# v8_8_controler.net
KiCad netlist of a schematic drawn in EAGLE
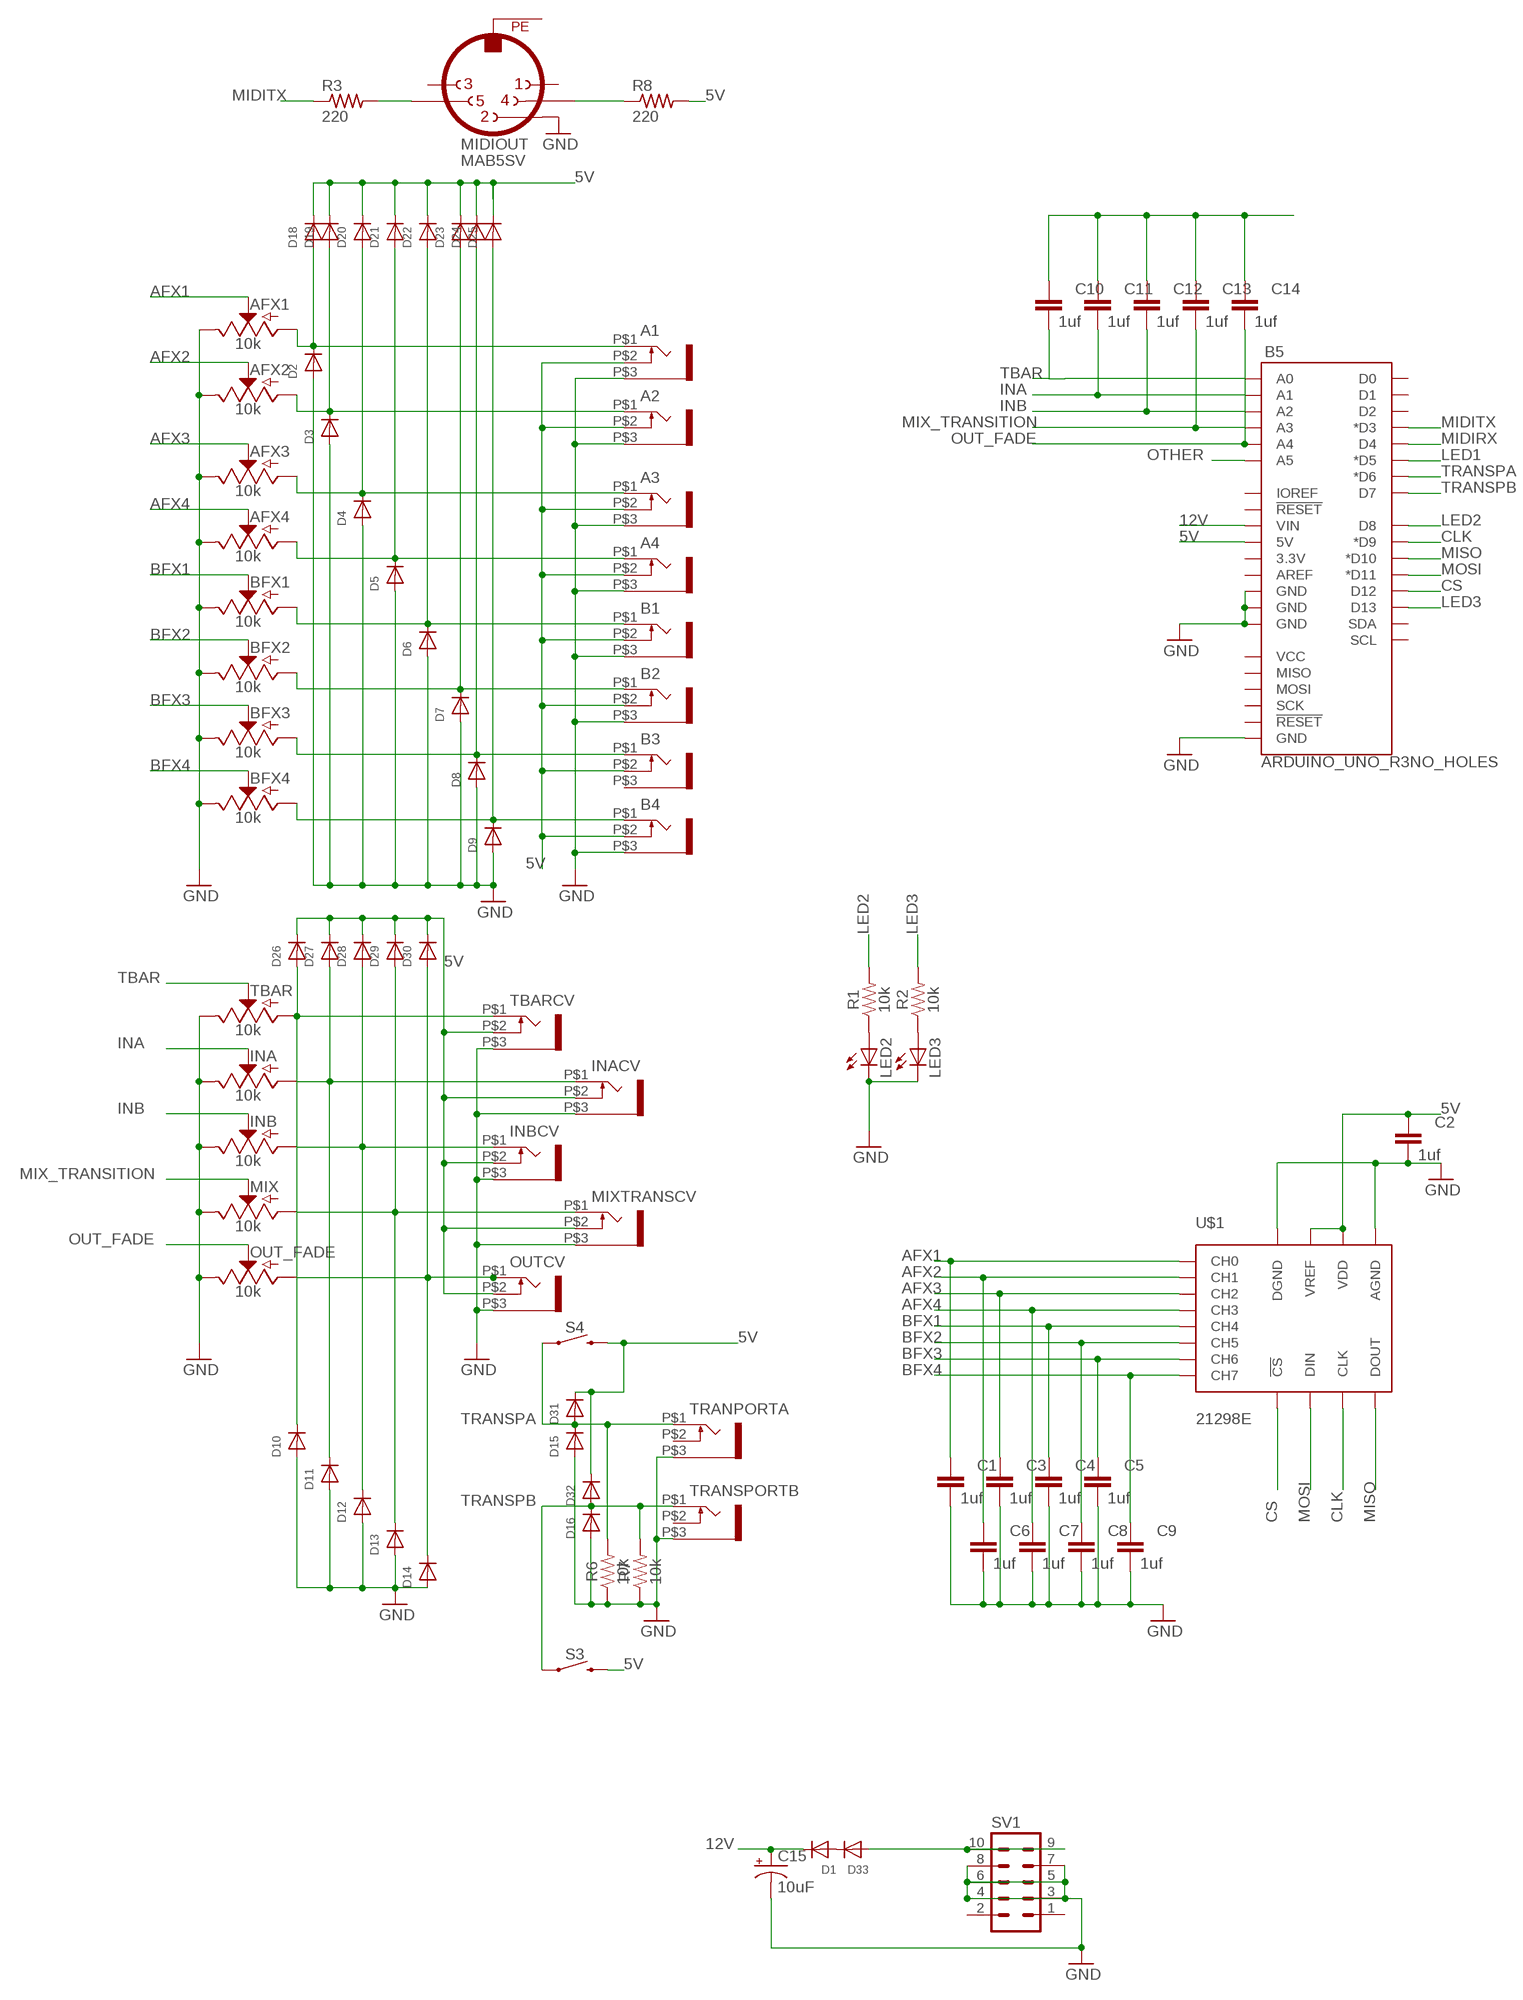
[diagram p0: schematic, sheet 1]

(export (version "E")
  (design (tool "Eeschema 10.0.6"))
  (components
    (comp (ref "A1")
      (value "WQP-PJ301M-12_JACK")
      (footprint "eagle-import:WQP-PJ301M-12_JACK")
      (fields (field (name "SPICEPREFIX") "U"))
      (libsource (lib "eagle-import") (part "WQP-PJ301M-12_JACK"))
    )
    (comp (ref "A2")
      (value "WQP-PJ301M-12_JACK")
      (footprint "eagle-import:WQP-PJ301M-12_JACK")
      (fields (field (name "SPICEPREFIX") "U"))
      (libsource (lib "eagle-import") (part "WQP-PJ301M-12_JACK"))
    )
    (comp (ref "A3")
      (value "WQP-PJ301M-12_JACK")
      (footprint "eagle-import:WQP-PJ301M-12_JACK")
      (fields (field (name "SPICEPREFIX") "U"))
      (libsource (lib "eagle-import") (part "WQP-PJ301M-12_JACK"))
    )
    (comp (ref "A4")
      (value "WQP-PJ301M-12_JACK")
      (footprint "eagle-import:WQP-PJ301M-12_JACK")
      (fields (field (name "SPICEPREFIX") "U"))
      (libsource (lib "eagle-import") (part "WQP-PJ301M-12_JACK"))
    )
    (comp (ref "AFX1")
      (value "10k")
      (footprint "eagle-import:POT-PTH-ALPS")
      (libsource (lib "eagle-import") (part "POTENTIOMETER-PTH-9MM-1/20W-20%"))
    )
    (comp (ref "AFX2")
      (value "10k")
      (footprint "eagle-import:POT-PTH-ALPS")
      (libsource (lib "eagle-import") (part "POTENTIOMETER-PTH-9MM-1/20W-20%"))
    )
    (comp (ref "AFX3")
      (value "10k")
      (footprint "eagle-import:POT-PTH-ALPS")
      (libsource (lib "eagle-import") (part "POTENTIOMETER-PTH-9MM-1/20W-20%"))
    )
    (comp (ref "AFX4")
      (value "10k")
      (footprint "eagle-import:POT-PTH-ALPS")
      (libsource (lib "eagle-import") (part "POTENTIOMETER-PTH-9MM-1/20W-20%"))
    )
    (comp (ref "B1")
      (value "WQP-PJ301M-12_JACK")
      (footprint "eagle-import:WQP-PJ301M-12_JACK")
      (fields (field (name "SPICEPREFIX") "U"))
      (libsource (lib "eagle-import") (part "WQP-PJ301M-12_JACK"))
    )
    (comp (ref "B2")
      (value "WQP-PJ301M-12_JACK")
      (footprint "eagle-import:WQP-PJ301M-12_JACK")
      (fields (field (name "SPICEPREFIX") "U"))
      (libsource (lib "eagle-import") (part "WQP-PJ301M-12_JACK"))
    )
    (comp (ref "B3")
      (value "WQP-PJ301M-12_JACK")
      (footprint "eagle-import:WQP-PJ301M-12_JACK")
      (fields (field (name "SPICEPREFIX") "U"))
      (libsource (lib "eagle-import") (part "WQP-PJ301M-12_JACK"))
    )
    (comp (ref "B4")
      (value "WQP-PJ301M-12_JACK")
      (footprint "eagle-import:WQP-PJ301M-12_JACK")
      (fields (field (name "SPICEPREFIX") "U"))
      (libsource (lib "eagle-import") (part "WQP-PJ301M-12_JACK"))
    )
    (comp (ref "B5")
      (value "ARDUINO_UNO_R3NO_HOLES")
      (footprint "eagle-import:ARDUINO_R3_NO_HOLES")
      (libsource (lib "eagle-import") (part "ARDUINO_UNO_R3NO_HOLES"))
    )
    (comp (ref "BFX1")
      (value "10k")
      (footprint "eagle-import:POT-PTH-ALPS")
      (libsource (lib "eagle-import") (part "POTENTIOMETER-PTH-9MM-1/20W-20%"))
    )
    (comp (ref "BFX2")
      (value "10k")
      (footprint "eagle-import:POT-PTH-ALPS")
      (libsource (lib "eagle-import") (part "POTENTIOMETER-PTH-9MM-1/20W-20%"))
    )
    (comp (ref "BFX3")
      (value "10k")
      (footprint "eagle-import:POT-PTH-ALPS")
      (libsource (lib "eagle-import") (part "POTENTIOMETER-PTH-9MM-1/20W-20%"))
    )
    (comp (ref "BFX4")
      (value "10k")
      (footprint "eagle-import:POT-PTH-ALPS")
      (libsource (lib "eagle-import") (part "POTENTIOMETER-PTH-9MM-1/20W-20%"))
    )
    (comp (ref "C1")
      (value "1uf")
      (footprint "eagle-import:0805")
      (libsource (lib "eagle-import") (part "0.33UF/330NF-0805-50V-10%"))
    )
    (comp (ref "C2")
      (value "1uf")
      (footprint "eagle-import:0805")
      (libsource (lib "eagle-import") (part "0.33UF/330NF-0805-50V-10%"))
    )
    (comp (ref "C3")
      (value "1uf")
      (footprint "eagle-import:0805")
      (libsource (lib "eagle-import") (part "0.33UF/330NF-0805-50V-10%"))
    )
    (comp (ref "C4")
      (value "1uf")
      (footprint "eagle-import:0805")
      (libsource (lib "eagle-import") (part "0.33UF/330NF-0805-50V-10%"))
    )
    (comp (ref "C5")
      (value "1uf")
      (footprint "eagle-import:0805")
      (libsource (lib "eagle-import") (part "0.33UF/330NF-0805-50V-10%"))
    )
    (comp (ref "C6")
      (value "1uf")
      (footprint "eagle-import:0805")
      (libsource (lib "eagle-import") (part "0.33UF/330NF-0805-50V-10%"))
    )
    (comp (ref "C7")
      (value "1uf")
      (footprint "eagle-import:0805")
      (libsource (lib "eagle-import") (part "0.33UF/330NF-0805-50V-10%"))
    )
    (comp (ref "C8")
      (value "1uf")
      (footprint "eagle-import:0805")
      (libsource (lib "eagle-import") (part "0.33UF/330NF-0805-50V-10%"))
    )
    (comp (ref "C9")
      (value "1uf")
      (footprint "eagle-import:0805")
      (libsource (lib "eagle-import") (part "0.33UF/330NF-0805-50V-10%"))
    )
    (comp (ref "C10")
      (value "1uf")
      (footprint "eagle-import:0805")
      (libsource (lib "eagle-import") (part "0.33UF/330NF-0805-50V-10%"))
    )
    (comp (ref "C11")
      (value "1uf")
      (footprint "eagle-import:0805")
      (libsource (lib "eagle-import") (part "0.33UF/330NF-0805-50V-10%"))
    )
    (comp (ref "C12")
      (value "1uf")
      (footprint "eagle-import:0805")
      (libsource (lib "eagle-import") (part "0.33UF/330NF-0805-50V-10%"))
    )
    (comp (ref "C13")
      (value "1uf")
      (footprint "eagle-import:0805")
      (libsource (lib "eagle-import") (part "0.33UF/330NF-0805-50V-10%"))
    )
    (comp (ref "C14")
      (value "1uf")
      (footprint "eagle-import:0805")
      (libsource (lib "eagle-import") (part "0.33UF/330NF-0805-50V-10%"))
    )
    (comp (ref "C15")
      (value "10uF")
      (footprint "eagle-import:EIA3528")
      (libsource (lib "eagle-import") (part "10UF-POLAR-EIA3528-20V-10%(TANT)"))
    )
    (comp (ref "D1")
      (value "DIODE_SOD-123FL")
      (footprint "eagle-import:SOD-123FL")
      (libsource (lib "eagle-import") (part "DIODE_SOD-123FL"))
    )
    (comp (ref "D2")
      (value "DIODE_SOD-123FL")
      (footprint "eagle-import:SOD-123FL")
      (libsource (lib "eagle-import") (part "DIODE_SOD-123FL"))
    )
    (comp (ref "D3")
      (value "DIODE_SOD-123FL")
      (footprint "eagle-import:SOD-123FL")
      (libsource (lib "eagle-import") (part "DIODE_SOD-123FL"))
    )
    (comp (ref "D4")
      (value "DIODE_SOD-123FL")
      (footprint "eagle-import:SOD-123FL")
      (libsource (lib "eagle-import") (part "DIODE_SOD-123FL"))
    )
    (comp (ref "D5")
      (value "DIODE_SOD-123FL")
      (footprint "eagle-import:SOD-123FL")
      (libsource (lib "eagle-import") (part "DIODE_SOD-123FL"))
    )
    (comp (ref "D6")
      (value "DIODE_SOD-123FL")
      (footprint "eagle-import:SOD-123FL")
      (libsource (lib "eagle-import") (part "DIODE_SOD-123FL"))
    )
    (comp (ref "D7")
      (value "DIODE_SOD-123FL")
      (footprint "eagle-import:SOD-123FL")
      (libsource (lib "eagle-import") (part "DIODE_SOD-123FL"))
    )
    (comp (ref "D8")
      (value "DIODE_SOD-123FL")
      (footprint "eagle-import:SOD-123FL")
      (libsource (lib "eagle-import") (part "DIODE_SOD-123FL"))
    )
    (comp (ref "D9")
      (value "DIODE_SOD-123FL")
      (footprint "eagle-import:SOD-123FL")
      (libsource (lib "eagle-import") (part "DIODE_SOD-123FL"))
    )
    (comp (ref "D10")
      (value "DIODE_SOD-123FL")
      (footprint "eagle-import:SOD-123FL")
      (libsource (lib "eagle-import") (part "DIODE_SOD-123FL"))
    )
    (comp (ref "D11")
      (value "DIODE_SOD-123FL")
      (footprint "eagle-import:SOD-123FL")
      (libsource (lib "eagle-import") (part "DIODE_SOD-123FL"))
    )
    (comp (ref "D12")
      (value "DIODE_SOD-123FL")
      (footprint "eagle-import:SOD-123FL")
      (libsource (lib "eagle-import") (part "DIODE_SOD-123FL"))
    )
    (comp (ref "D13")
      (value "DIODE_SOD-123FL")
      (footprint "eagle-import:SOD-123FL")
      (libsource (lib "eagle-import") (part "DIODE_SOD-123FL"))
    )
    (comp (ref "D14")
      (value "DIODE_SOD-123FL")
      (footprint "eagle-import:SOD-123FL")
      (libsource (lib "eagle-import") (part "DIODE_SOD-123FL"))
    )
    (comp (ref "D15")
      (value "DIODE_SOD-123FL")
      (footprint "eagle-import:SOD-123FL")
      (libsource (lib "eagle-import") (part "DIODE_SOD-123FL"))
    )
    (comp (ref "D16")
      (value "DIODE_SOD-123FL")
      (footprint "eagle-import:SOD-123FL")
      (libsource (lib "eagle-import") (part "DIODE_SOD-123FL"))
    )
    (comp (ref "D18")
      (value "DIODE_SOD-123FL")
      (footprint "eagle-import:SOD-123FL")
      (libsource (lib "eagle-import") (part "DIODE_SOD-123FL"))
    )
    (comp (ref "D19")
      (value "DIODE_SOD-123FL")
      (footprint "eagle-import:SOD-123FL")
      (libsource (lib "eagle-import") (part "DIODE_SOD-123FL"))
    )
    (comp (ref "D20")
      (value "DIODE_SOD-123FL")
      (footprint "eagle-import:SOD-123FL")
      (libsource (lib "eagle-import") (part "DIODE_SOD-123FL"))
    )
    (comp (ref "D21")
      (value "DIODE_SOD-123FL")
      (footprint "eagle-import:SOD-123FL")
      (libsource (lib "eagle-import") (part "DIODE_SOD-123FL"))
    )
    (comp (ref "D22")
      (value "DIODE_SOD-123FL")
      (footprint "eagle-import:SOD-123FL")
      (libsource (lib "eagle-import") (part "DIODE_SOD-123FL"))
    )
    (comp (ref "D23")
      (value "DIODE_SOD-123FL")
      (footprint "eagle-import:SOD-123FL")
      (libsource (lib "eagle-import") (part "DIODE_SOD-123FL"))
    )
    (comp (ref "D24")
      (value "DIODE_SOD-123FL")
      (footprint "eagle-import:SOD-123FL")
      (libsource (lib "eagle-import") (part "DIODE_SOD-123FL"))
    )
    (comp (ref "D25")
      (value "DIODE_SOD-123FL")
      (footprint "eagle-import:SOD-123FL")
      (libsource (lib "eagle-import") (part "DIODE_SOD-123FL"))
    )
    (comp (ref "D26")
      (value "DIODE_SOD-123FL")
      (footprint "eagle-import:SOD-123FL")
      (libsource (lib "eagle-import") (part "DIODE_SOD-123FL"))
    )
    (comp (ref "D27")
      (value "DIODE_SOD-123FL")
      (footprint "eagle-import:SOD-123FL")
      (libsource (lib "eagle-import") (part "DIODE_SOD-123FL"))
    )
    (comp (ref "D28")
      (value "DIODE_SOD-123FL")
      (footprint "eagle-import:SOD-123FL")
      (libsource (lib "eagle-import") (part "DIODE_SOD-123FL"))
    )
    (comp (ref "D29")
      (value "DIODE_SOD-123FL")
      (footprint "eagle-import:SOD-123FL")
      (libsource (lib "eagle-import") (part "DIODE_SOD-123FL"))
    )
    (comp (ref "D30")
      (value "DIODE_SOD-123FL")
      (footprint "eagle-import:SOD-123FL")
      (libsource (lib "eagle-import") (part "DIODE_SOD-123FL"))
    )
    (comp (ref "D31")
      (value "DIODE_SOD-123FL")
      (footprint "eagle-import:SOD-123FL")
      (libsource (lib "eagle-import") (part "DIODE_SOD-123FL"))
    )
    (comp (ref "D32")
      (value "DIODE_SOD-123FL")
      (footprint "eagle-import:SOD-123FL")
      (libsource (lib "eagle-import") (part "DIODE_SOD-123FL"))
    )
    (comp (ref "D33")
      (value "DIODE_SOD-123FL")
      (footprint "eagle-import:SOD-123FL")
      (libsource (lib "eagle-import") (part "DIODE_SOD-123FL"))
    )
    (comp (ref "INA")
      (value "10k")
      (footprint "eagle-import:POT-PTH-ALPS")
      (libsource (lib "eagle-import") (part "POTENTIOMETER-PTH-9MM-1/20W-20%"))
    )
    (comp (ref "INACV")
      (value "WQP-PJ301M-12_JACK")
      (footprint "eagle-import:WQP-PJ301M-12_JACK")
      (fields (field (name "SPICEPREFIX") "U"))
      (libsource (lib "eagle-import") (part "WQP-PJ301M-12_JACK"))
    )
    (comp (ref "INB")
      (value "10k")
      (footprint "eagle-import:POT-PTH-ALPS")
      (libsource (lib "eagle-import") (part "POTENTIOMETER-PTH-9MM-1/20W-20%"))
    )
    (comp (ref "INBCV")
      (value "WQP-PJ301M-12_JACK")
      (footprint "eagle-import:WQP-PJ301M-12_JACK")
      (fields (field (name "SPICEPREFIX") "U"))
      (libsource (lib "eagle-import") (part "WQP-PJ301M-12_JACK"))
    )
    (comp (ref "LED2")
      (value "LED3MM")
      (footprint "eagle-import:LED3MM")
      (libsource (lib "eagle-import") (part "LED3MM"))
    )
    (comp (ref "LED3")
      (value "LED3MM")
      (footprint "eagle-import:LED3MM")
      (libsource (lib "eagle-import") (part "LED3MM"))
    )
    (comp (ref "MIDIOUT")
      (value "MAB5SV")
      (footprint "eagle-import:MAB5SV")
      (libsource (lib "eagle-import") (part "MAB5SV"))
    )
    (comp (ref "MIX")
      (value "10k")
      (footprint "eagle-import:POT-PTH-ALPS")
      (libsource (lib "eagle-import") (part "POTENTIOMETER-PTH-9MM-1/20W-20%"))
    )
    (comp (ref "MIXTRANSCV")
      (value "WQP-PJ301M-12_JACK")
      (footprint "eagle-import:WQP-PJ301M-12_JACK")
      (fields (field (name "SPICEPREFIX") "U"))
      (libsource (lib "eagle-import") (part "WQP-PJ301M-12_JACK"))
    )
    (comp (ref "OUTCV")
      (value "WQP-PJ301M-12_JACK")
      (footprint "eagle-import:WQP-PJ301M-12_JACK")
      (fields (field (name "SPICEPREFIX") "U"))
      (libsource (lib "eagle-import") (part "WQP-PJ301M-12_JACK"))
    )
    (comp (ref "OUT_FADE")
      (value "10k")
      (footprint "eagle-import:POT-PTH-ALPS")
      (libsource (lib "eagle-import") (part "POTENTIOMETER-PTH-9MM-1/20W-20%"))
    )
    (comp (ref "R1")
      (value "10k")
      (footprint "eagle-import:0805")
      (libsource (lib "eagle-import") (part "0.75OHM-0805-1/4W-1%"))
    )
    (comp (ref "R2")
      (value "10k")
      (footprint "eagle-import:0805")
      (libsource (lib "eagle-import") (part "0.75OHM-0805-1/4W-1%"))
    )
    (comp (ref "R3")
      (value "220")
      (footprint "eagle-import:R0805")
      (libsource (lib "eagle-import") (part "R-US_R0805"))
    )
    (comp (ref "R6")
      (value "10k")
      (footprint "eagle-import:0805")
      (libsource (lib "eagle-import") (part "0.75OHM-0805-1/4W-1%"))
    )
    (comp (ref "R7")
      (value "10k")
      (footprint "eagle-import:0805")
      (libsource (lib "eagle-import") (part "0.75OHM-0805-1/4W-1%"))
    )
    (comp (ref "R8")
      (value "220")
      (footprint "eagle-import:R0805")
      (libsource (lib "eagle-import") (part "R-US_R0805"))
    )
    (comp (ref "S3")
      (value "MOMENTARY-SWITCH-SPST-PTH-6.0MM")
      (footprint "eagle-import:TACTILE_SWITCH_PTH_6.0MM")
      (libsource (lib "eagle-import") (part "MOMENTARY-SWITCH-SPST-PTH-6.0MM"))
    )
    (comp (ref "S4")
      (value "MOMENTARY-SWITCH-SPST-PTH-6.0MM")
      (footprint "eagle-import:TACTILE_SWITCH_PTH_6.0MM")
      (libsource (lib "eagle-import") (part "MOMENTARY-SWITCH-SPST-PTH-6.0MM"))
    )
    (comp (ref "SV1")
      (value "MA05-2")
      (footprint "eagle-import:MA05-2")
      (libsource (lib "eagle-import") (part "MA05-2"))
    )
    (comp (ref "TBAR")
      (value "10k")
      (footprint "eagle-import:POT-PTH-ALPS")
      (libsource (lib "eagle-import") (part "POTENTIOMETER-PTH-9MM-1/20W-20%"))
    )
    (comp (ref "TBARCV")
      (value "WQP-PJ301M-12_JACK")
      (footprint "eagle-import:WQP-PJ301M-12_JACK")
      (fields (field (name "SPICEPREFIX") "U"))
      (libsource (lib "eagle-import") (part "WQP-PJ301M-12_JACK"))
    )
    (comp (ref "TRANPORTA")
      (value "WQP-PJ301M-12_JACK")
      (footprint "eagle-import:WQP-PJ301M-12_JACK")
      (fields (field (name "SPICEPREFIX") "U"))
      (libsource (lib "eagle-import") (part "WQP-PJ301M-12_JACK"))
    )
    (comp (ref "TRANSPORTB")
      (value "WQP-PJ301M-12_JACK")
      (footprint "eagle-import:WQP-PJ301M-12_JACK")
      (fields (field (name "SPICEPREFIX") "U"))
      (libsource (lib "eagle-import") (part "WQP-PJ301M-12_JACK"))
    )
    (comp (ref "U$1")
      (value "21298E")
      (footprint "eagle-import:PDIP16")
      (libsource (lib "eagle-import") (part "21298E"))
    )
  )
  (nets
    (net (code "1") (name "/5V") (class "Default")
      (node (ref "A1") (pin "P$2") (pinfunction "3_P$2") (pintype "passive"))
      (node (ref "A2") (pin "P$2") (pinfunction "3_P$2") (pintype "passive"))
      (node (ref "A3") (pin "P$2") (pinfunction "3_P$2") (pintype "passive"))
      (node (ref "A4") (pin "P$2") (pinfunction "3_P$2") (pintype "passive"))
      (node (ref "B1") (pin "P$2") (pinfunction "3_P$2") (pintype "passive"))
      (node (ref "B2") (pin "P$2") (pinfunction "3_P$2") (pintype "passive"))
      (node (ref "B3") (pin "P$2") (pinfunction "3_P$2") (pintype "passive"))
      (node (ref "B4") (pin "P$2") (pinfunction "3_P$2") (pintype "passive"))
      (node (ref "B5") (pin "5V") (pinfunction "5V_5V") (pintype "bidirectional"))
      (node (ref "C2") (pin "1") (pinfunction "1_1") (pintype "passive"))
      (node (ref "D18") (pin "C") (pinfunction "C_C") (pintype "passive"))
      (node (ref "D19") (pin "C") (pinfunction "C_C") (pintype "passive"))
      (node (ref "D20") (pin "C") (pinfunction "C_C") (pintype "passive"))
      (node (ref "D21") (pin "C") (pinfunction "C_C") (pintype "passive"))
      (node (ref "D22") (pin "C") (pinfunction "C_C") (pintype "passive"))
      (node (ref "D23") (pin "C") (pinfunction "C_C") (pintype "passive"))
      (node (ref "D24") (pin "C") (pinfunction "C_C") (pintype "passive"))
      (node (ref "D25") (pin "C") (pinfunction "C_C") (pintype "passive"))
      (node (ref "D26") (pin "C") (pinfunction "C_C") (pintype "passive"))
      (node (ref "D27") (pin "C") (pinfunction "C_C") (pintype "passive"))
      (node (ref "D28") (pin "C") (pinfunction "C_C") (pintype "passive"))
      (node (ref "D29") (pin "C") (pinfunction "C_C") (pintype "passive"))
      (node (ref "D30") (pin "C") (pinfunction "C_C") (pintype "passive"))
      (node (ref "D31") (pin "C") (pinfunction "C_C") (pintype "passive"))
      (node (ref "D32") (pin "C") (pinfunction "C_C") (pintype "passive"))
      (node (ref "INACV") (pin "P$2") (pinfunction "3_P$2") (pintype "passive"))
      (node (ref "INBCV") (pin "P$2") (pinfunction "3_P$2") (pintype "passive"))
      (node (ref "MIXTRANSCV") (pin "P$2") (pinfunction "3_P$2") (pintype "passive"))
      (node (ref "OUTCV") (pin "P$2") (pinfunction "3_P$2") (pintype "passive"))
      (node (ref "R8") (pin "2") (pinfunction "2_2") (pintype "passive"))
      (node (ref "S3") (pin "3") (pinfunction "2_3") (pintype "passive"))
      (node (ref "S4") (pin "3") (pinfunction "2_3") (pintype "passive"))
      (node (ref "TBARCV") (pin "P$2") (pinfunction "3_P$2") (pintype "passive"))
      (node (ref "U$1") (pin "P$15") (pinfunction "VREF_P$15") (pintype "bidirectional"))
      (node (ref "U$1") (pin "P$16") (pinfunction "VDD_P$16") (pintype "bidirectional"))
    )
    (net (code "2") (name "/12V") (class "Default")
      (node (ref "B5") (pin "VIN") (pinfunction "VIN_VIN") (pintype "bidirectional"))
      (node (ref "C15") (pin "A") (pinfunction "+_A") (pintype "passive"))
      (node (ref "D1") (pin "C") (pinfunction "C_C") (pintype "passive"))
    )
    (net (code "3") (name "/AFX1") (class "Default")
      (node (ref "AFX1") (pin "P$2") (pinfunction "S_P$2") (pintype "passive"))
      (node (ref "C1") (pin "1") (pinfunction "1_1") (pintype "passive"))
      (node (ref "U$1") (pin "P$1") (pinfunction "CH0_P$1") (pintype "bidirectional"))
    )
    (net (code "4") (name "/AFX2") (class "Default")
      (node (ref "AFX2") (pin "P$2") (pinfunction "S_P$2") (pintype "passive"))
      (node (ref "C6") (pin "1") (pinfunction "1_1") (pintype "passive"))
      (node (ref "U$1") (pin "P$2") (pinfunction "CH1_P$2") (pintype "bidirectional"))
    )
    (net (code "5") (name "/AFX3") (class "Default")
      (node (ref "AFX3") (pin "P$2") (pinfunction "S_P$2") (pintype "passive"))
      (node (ref "C3") (pin "1") (pinfunction "1_1") (pintype "passive"))
      (node (ref "U$1") (pin "P$3") (pinfunction "CH2_P$3") (pintype "bidirectional"))
    )
    (net (code "6") (name "/AFX4") (class "Default")
      (node (ref "AFX4") (pin "P$2") (pinfunction "S_P$2") (pintype "passive"))
      (node (ref "C7") (pin "1") (pinfunction "1_1") (pintype "passive"))
      (node (ref "U$1") (pin "P$4") (pinfunction "CH3_P$4") (pintype "bidirectional"))
    )
    (net (code "7") (name "/BFX1") (class "Default")
      (node (ref "BFX1") (pin "P$2") (pinfunction "S_P$2") (pintype "passive"))
      (node (ref "C4") (pin "1") (pinfunction "1_1") (pintype "passive"))
      (node (ref "U$1") (pin "P$5") (pinfunction "CH4_P$5") (pintype "bidirectional"))
    )
    (net (code "8") (name "/BFX2") (class "Default")
      (node (ref "BFX2") (pin "P$2") (pinfunction "S_P$2") (pintype "passive"))
      (node (ref "C8") (pin "1") (pinfunction "1_1") (pintype "passive"))
      (node (ref "U$1") (pin "P$6") (pinfunction "CH5_P$6") (pintype "bidirectional"))
    )
    (net (code "9") (name "/BFX3") (class "Default")
      (node (ref "BFX3") (pin "P$2") (pinfunction "S_P$2") (pintype "passive"))
      (node (ref "C5") (pin "1") (pinfunction "1_1") (pintype "passive"))
      (node (ref "U$1") (pin "P$7") (pinfunction "CH6_P$7") (pintype "bidirectional"))
    )
    (net (code "10") (name "/BFX4") (class "Default")
      (node (ref "BFX4") (pin "P$2") (pinfunction "S_P$2") (pintype "passive"))
      (node (ref "C9") (pin "1") (pinfunction "1_1") (pintype "passive"))
      (node (ref "U$1") (pin "P$8") (pinfunction "CH7_P$8") (pintype "bidirectional"))
    )
    (net (code "11") (name "/CLK") (class "Default")
      (node (ref "B5") (pin "D9") (pinfunction "*D9_D9") (pintype "bidirectional"))
      (node (ref "U$1") (pin "P$13") (pinfunction "CLK_P$13") (pintype "bidirectional"))
    )
    (net (code "12") (name "/CS") (class "Default")
      (node (ref "B5") (pin "D12") (pinfunction "D12_D12") (pintype "bidirectional"))
      (node (ref "U$1") (pin "P$10") (pinfunction "~{CS}_P$10") (pintype "bidirectional"))
    )
    (net (code "13") (name "/INA") (class "Default")
      (node (ref "B5") (pin "A1") (pinfunction "A1_A1") (pintype "bidirectional"))
      (node (ref "C11") (pin "2") (pinfunction "2_2") (pintype "passive"))
      (node (ref "INA") (pin "P$2") (pinfunction "S_P$2") (pintype "passive"))
    )
    (net (code "14") (name "/INB") (class "Default")
      (node (ref "B5") (pin "A2") (pinfunction "A2_A2") (pintype "bidirectional"))
      (node (ref "C12") (pin "2") (pinfunction "2_2") (pintype "passive"))
      (node (ref "INB") (pin "P$2") (pinfunction "S_P$2") (pintype "passive"))
    )
    (net (code "15") (name "/LED1") (class "Default")
      (node (ref "B5") (pin "D5") (pinfunction "*D5_D5") (pintype "bidirectional"))
    )
    (net (code "16") (name "/LED2") (class "Default")
      (node (ref "B5") (pin "D8") (pinfunction "D8_D8") (pintype "bidirectional"))
      (node (ref "R1") (pin "2") (pinfunction "2_2") (pintype "passive"))
    )
    (net (code "17") (name "/LED3") (class "Default")
      (node (ref "B5") (pin "D13") (pinfunction "D13_D13") (pintype "bidirectional"))
      (node (ref "R2") (pin "2") (pinfunction "2_2") (pintype "passive"))
    )
    (net (code "18") (name "/MIDIRX") (class "Default")
      (node (ref "B5") (pin "D4") (pinfunction "D4_D4") (pintype "bidirectional"))
    )
    (net (code "19") (name "/MIDITX") (class "Default")
      (node (ref "B5") (pin "D3") (pinfunction "*D3_D3") (pintype "bidirectional"))
      (node (ref "R3") (pin "1") (pinfunction "1_1") (pintype "passive"))
    )
    (net (code "20") (name "/MISO") (class "Default")
      (node (ref "B5") (pin "D10") (pinfunction "*D10_D10") (pintype "bidirectional"))
      (node (ref "U$1") (pin "P$12") (pinfunction "DOUT_P$12") (pintype "bidirectional"))
    )
    (net (code "21") (name "/MIX_TRANSITION") (class "Default")
      (node (ref "B5") (pin "A3") (pinfunction "A3_A3") (pintype "bidirectional"))
      (node (ref "C13") (pin "2") (pinfunction "2_2") (pintype "passive"))
      (node (ref "MIX") (pin "P$2") (pinfunction "S_P$2") (pintype "passive"))
    )
    (net (code "22") (name "/MOSI") (class "Default")
      (node (ref "B5") (pin "D11") (pinfunction "*D11_D11") (pintype "bidirectional"))
      (node (ref "U$1") (pin "P$11") (pinfunction "DIN_P$11") (pintype "bidirectional"))
    )
    (net (code "23") (name "/OTHER") (class "Default")
      (node (ref "B5") (pin "A5") (pinfunction "A5_A5") (pintype "bidirectional"))
    )
    (net (code "24") (name "/OUT_FADE") (class "Default")
      (node (ref "B5") (pin "A4") (pinfunction "A4_A4") (pintype "bidirectional"))
      (node (ref "C14") (pin "2") (pinfunction "2_2") (pintype "passive"))
      (node (ref "OUT_FADE") (pin "P$2") (pinfunction "S_P$2") (pintype "passive"))
    )
    (net (code "25") (name "/PE") (class "Default")
      (node (ref "MIDIOUT") (pin "PE") (pinfunction "PE_PE") (pintype "power_in"))
    )
    (net (code "26") (name "/TBAR") (class "Default")
      (node (ref "B5") (pin "A0") (pinfunction "A0_A0") (pintype "bidirectional"))
      (node (ref "C10") (pin "2") (pinfunction "2_2") (pintype "passive"))
      (node (ref "TBAR") (pin "P$2") (pinfunction "S_P$2") (pintype "passive"))
    )
    (net (code "27") (name "/TRANSPA") (class "Default")
      (node (ref "B5") (pin "D6") (pinfunction "*D6_D6") (pintype "bidirectional"))
      (node (ref "D15") (pin "C") (pinfunction "C_C") (pintype "passive"))
      (node (ref "D31") (pin "A") (pinfunction "A_A") (pintype "passive"))
      (node (ref "R6") (pin "2") (pinfunction "2_2") (pintype "passive"))
      (node (ref "S4") (pin "1") (pinfunction "1_1") (pintype "passive"))
      (node (ref "TRANPORTA") (pin "P$1") (pinfunction "2_P$1") (pintype "passive"))
    )
    (net (code "28") (name "/TRANSPB") (class "Default")
      (node (ref "B5") (pin "D7") (pinfunction "D7_D7") (pintype "bidirectional"))
      (node (ref "D16") (pin "C") (pinfunction "C_C") (pintype "passive"))
      (node (ref "D32") (pin "A") (pinfunction "A_A") (pintype "passive"))
      (node (ref "R7") (pin "2") (pinfunction "2_2") (pintype "passive"))
      (node (ref "S3") (pin "1") (pinfunction "1_1") (pintype "passive"))
      (node (ref "TRANSPORTB") (pin "P$1") (pinfunction "2_P$1") (pintype "passive"))
    )
    (net (code "29") (name "GND") (class "Default")
      (node (ref "A1") (pin "P$3") (pinfunction "1_P$3") (pintype "passive"))
      (node (ref "A2") (pin "P$3") (pinfunction "1_P$3") (pintype "passive"))
      (node (ref "A3") (pin "P$3") (pinfunction "1_P$3") (pintype "passive"))
      (node (ref "A4") (pin "P$3") (pinfunction "1_P$3") (pintype "passive"))
      (node (ref "AFX1") (pin "P$1") (pinfunction "E_P$1") (pintype "passive"))
      (node (ref "AFX2") (pin "P$1") (pinfunction "E_P$1") (pintype "passive"))
      (node (ref "AFX3") (pin "P$1") (pinfunction "E_P$1") (pintype "passive"))
      (node (ref "AFX4") (pin "P$1") (pinfunction "E_P$1") (pintype "passive"))
      (node (ref "B1") (pin "P$3") (pinfunction "1_P$3") (pintype "passive"))
      (node (ref "B2") (pin "P$3") (pinfunction "1_P$3") (pintype "passive"))
      (node (ref "B4") (pin "P$3") (pinfunction "1_P$3") (pintype "passive"))
      (node (ref "B5") (pin "GND@1") (pinfunction "GND_GND@1") (pintype "bidirectional"))
      (node (ref "B5") (pin "GND@2") (pinfunction "GND_GND@2") (pintype "bidirectional"))
      (node (ref "B5") (pin "GND@3") (pinfunction "GND_GND@3") (pintype "bidirectional"))
      (node (ref "B5") (pin "GND@4") (pinfunction "GND_GND@4") (pintype "bidirectional"))
      (node (ref "BFX1") (pin "P$1") (pinfunction "E_P$1") (pintype "passive"))
      (node (ref "BFX2") (pin "P$1") (pinfunction "E_P$1") (pintype "passive"))
      (node (ref "BFX3") (pin "P$1") (pinfunction "E_P$1") (pintype "passive"))
      (node (ref "BFX4") (pin "P$1") (pinfunction "E_P$1") (pintype "passive"))
      (node (ref "C1") (pin "2") (pinfunction "2_2") (pintype "passive"))
      (node (ref "C15") (pin "C") (pinfunction "-_C") (pintype "passive"))
      (node (ref "C2") (pin "2") (pinfunction "2_2") (pintype "passive"))
      (node (ref "C3") (pin "2") (pinfunction "2_2") (pintype "passive"))
      (node (ref "C4") (pin "2") (pinfunction "2_2") (pintype "passive"))
      (node (ref "C5") (pin "2") (pinfunction "2_2") (pintype "passive"))
      (node (ref "C6") (pin "2") (pinfunction "2_2") (pintype "passive"))
      (node (ref "C7") (pin "2") (pinfunction "2_2") (pintype "passive"))
      (node (ref "C8") (pin "2") (pinfunction "2_2") (pintype "passive"))
      (node (ref "C9") (pin "2") (pinfunction "2_2") (pintype "passive"))
      (node (ref "D10") (pin "A") (pinfunction "A_A") (pintype "passive"))
      (node (ref "D11") (pin "A") (pinfunction "A_A") (pintype "passive"))
      (node (ref "D12") (pin "A") (pinfunction "A_A") (pintype "passive"))
      (node (ref "D13") (pin "A") (pinfunction "A_A") (pintype "passive"))
      (node (ref "D14") (pin "A") (pinfunction "A_A") (pintype "passive"))
      (node (ref "D15") (pin "A") (pinfunction "A_A") (pintype "passive"))
      (node (ref "D16") (pin "A") (pinfunction "A_A") (pintype "passive"))
      (node (ref "D2") (pin "A") (pinfunction "A_A") (pintype "passive"))
      (node (ref "D3") (pin "A") (pinfunction "A_A") (pintype "passive"))
      (node (ref "D4") (pin "A") (pinfunction "A_A") (pintype "passive"))
      (node (ref "D5") (pin "A") (pinfunction "A_A") (pintype "passive"))
      (node (ref "D6") (pin "A") (pinfunction "A_A") (pintype "passive"))
      (node (ref "D7") (pin "A") (pinfunction "A_A") (pintype "passive"))
      (node (ref "D8") (pin "A") (pinfunction "A_A") (pintype "passive"))
      (node (ref "D9") (pin "A") (pinfunction "A_A") (pintype "passive"))
      (node (ref "INA") (pin "P$1") (pinfunction "E_P$1") (pintype "passive"))
      (node (ref "INACV") (pin "P$3") (pinfunction "1_P$3") (pintype "passive"))
      (node (ref "INB") (pin "P$1") (pinfunction "E_P$1") (pintype "passive"))
      (node (ref "INBCV") (pin "P$3") (pinfunction "1_P$3") (pintype "passive"))
      (node (ref "LED2") (pin "K") (pinfunction "C_K") (pintype "passive"))
      (node (ref "LED3") (pin "K") (pinfunction "C_K") (pintype "passive"))
      (node (ref "MIDIOUT") (pin "2") (pinfunction "2_2") (pintype "passive"))
      (node (ref "MIX") (pin "P$1") (pinfunction "E_P$1") (pintype "passive"))
      (node (ref "MIXTRANSCV") (pin "P$3") (pinfunction "1_P$3") (pintype "passive"))
      (node (ref "OUTCV") (pin "P$3") (pinfunction "1_P$3") (pintype "passive"))
      (node (ref "OUT_FADE") (pin "P$1") (pinfunction "E_P$1") (pintype "passive"))
      (node (ref "R6") (pin "1") (pinfunction "1_1") (pintype "passive"))
      (node (ref "R7") (pin "1") (pinfunction "1_1") (pintype "passive"))
      (node (ref "SV1") (pin "3") (pinfunction "3_3") (pintype "passive"))
      (node (ref "SV1") (pin "4") (pinfunction "4_4") (pintype "passive"))
      (node (ref "SV1") (pin "5") (pinfunction "5_5") (pintype "passive"))
      (node (ref "SV1") (pin "6") (pinfunction "6_6") (pintype "passive"))
      (node (ref "SV1") (pin "7") (pinfunction "7_7") (pintype "passive"))
      (node (ref "SV1") (pin "8") (pinfunction "8_8") (pintype "passive"))
      (node (ref "TBAR") (pin "P$1") (pinfunction "E_P$1") (pintype "passive"))
      (node (ref "TBARCV") (pin "P$3") (pinfunction "1_P$3") (pintype "passive"))
      (node (ref "TRANPORTA") (pin "P$3") (pinfunction "1_P$3") (pintype "passive"))
      (node (ref "TRANSPORTB") (pin "P$3") (pinfunction "1_P$3") (pintype "passive"))
      (node (ref "U$1") (pin "P$14") (pinfunction "AGND_P$14") (pintype "bidirectional"))
      (node (ref "U$1") (pin "P$9") (pinfunction "DGND_P$9") (pintype "bidirectional"))
    )
    (net (code "30") (name "Net-(A1-2)") (class "Default")
      (node (ref "A1") (pin "P$1") (pinfunction "2_P$1") (pintype "passive"))
      (node (ref "AFX1") (pin "P$3") (pinfunction "A_P$3") (pintype "passive"))
      (node (ref "D18") (pin "A") (pinfunction "A_A") (pintype "passive"))
      (node (ref "D2") (pin "C") (pinfunction "C_C") (pintype "passive"))
    )
    (net (code "31") (name "Net-(A2-2)") (class "Default")
      (node (ref "A2") (pin "P$1") (pinfunction "2_P$1") (pintype "passive"))
      (node (ref "AFX2") (pin "P$3") (pinfunction "A_P$3") (pintype "passive"))
      (node (ref "D19") (pin "A") (pinfunction "A_A") (pintype "passive"))
      (node (ref "D3") (pin "C") (pinfunction "C_C") (pintype "passive"))
    )
    (net (code "32") (name "Net-(A3-2)") (class "Default")
      (node (ref "A3") (pin "P$1") (pinfunction "2_P$1") (pintype "passive"))
      (node (ref "AFX3") (pin "P$3") (pinfunction "A_P$3") (pintype "passive"))
      (node (ref "D20") (pin "A") (pinfunction "A_A") (pintype "passive"))
      (node (ref "D4") (pin "C") (pinfunction "C_C") (pintype "passive"))
    )
    (net (code "33") (name "Net-(A4-2)") (class "Default")
      (node (ref "A4") (pin "P$1") (pinfunction "2_P$1") (pintype "passive"))
      (node (ref "AFX4") (pin "P$3") (pinfunction "A_P$3") (pintype "passive"))
      (node (ref "D21") (pin "A") (pinfunction "A_A") (pintype "passive"))
      (node (ref "D5") (pin "C") (pinfunction "C_C") (pintype "passive"))
    )
    (net (code "34") (name "Net-(B1-2)") (class "Default")
      (node (ref "B1") (pin "P$1") (pinfunction "2_P$1") (pintype "passive"))
      (node (ref "BFX1") (pin "P$3") (pinfunction "A_P$3") (pintype "passive"))
      (node (ref "D22") (pin "A") (pinfunction "A_A") (pintype "passive"))
      (node (ref "D6") (pin "C") (pinfunction "C_C") (pintype "passive"))
    )
    (net (code "35") (name "Net-(B2-2)") (class "Default")
      (node (ref "B2") (pin "P$1") (pinfunction "2_P$1") (pintype "passive"))
      (node (ref "BFX2") (pin "P$3") (pinfunction "A_P$3") (pintype "passive"))
      (node (ref "D23") (pin "A") (pinfunction "A_A") (pintype "passive"))
      (node (ref "D7") (pin "C") (pinfunction "C_C") (pintype "passive"))
    )
    (net (code "36") (name "Net-(B3-2)") (class "Default")
      (node (ref "B3") (pin "P$1") (pinfunction "2_P$1") (pintype "passive"))
      (node (ref "BFX3") (pin "P$3") (pinfunction "A_P$3") (pintype "passive"))
      (node (ref "D24") (pin "A") (pinfunction "A_A") (pintype "passive"))
      (node (ref "D8") (pin "C") (pinfunction "C_C") (pintype "passive"))
    )
    (net (code "37") (name "Net-(B4-2)") (class "Default")
      (node (ref "B4") (pin "P$1") (pinfunction "2_P$1") (pintype "passive"))
      (node (ref "BFX4") (pin "P$3") (pinfunction "A_P$3") (pintype "passive"))
      (node (ref "D25") (pin "A") (pinfunction "A_A") (pintype "passive"))
      (node (ref "D9") (pin "C") (pinfunction "C_C") (pintype "passive"))
    )
    (net (code "38") (name "Net-(C10-Pad1)") (class "Default")
      (node (ref "C10") (pin "1") (pinfunction "1_1") (pintype "passive"))
      (node (ref "C11") (pin "1") (pinfunction "1_1") (pintype "passive"))
      (node (ref "C12") (pin "1") (pinfunction "1_1") (pintype "passive"))
      (node (ref "C13") (pin "1") (pinfunction "1_1") (pintype "passive"))
      (node (ref "C14") (pin "1") (pinfunction "1_1") (pintype "passive"))
    )
    (net (code "39") (name "Net-(D1-PadA)") (class "Default")
      (node (ref "D1") (pin "A") (pinfunction "A_A") (pintype "passive"))
      (node (ref "D33") (pin "C") (pinfunction "C_C") (pintype "passive"))
    )
    (net (code "40") (name "Net-(D33-PadA)") (class "Default")
      (node (ref "D33") (pin "A") (pinfunction "A_A") (pintype "passive"))
      (node (ref "SV1") (pin "10") (pinfunction "10_10") (pintype "passive"))
      (node (ref "SV1") (pin "9") (pinfunction "9_9") (pintype "passive"))
    )
    (net (code "41") (name "Net-(INA-A)") (class "Default")
      (node (ref "D11") (pin "C") (pinfunction "C_C") (pintype "passive"))
      (node (ref "D27") (pin "A") (pinfunction "A_A") (pintype "passive"))
      (node (ref "INA") (pin "P$3") (pinfunction "A_P$3") (pintype "passive"))
      (node (ref "INACV") (pin "P$1") (pinfunction "2_P$1") (pintype "passive"))
    )
    (net (code "42") (name "Net-(INB-A)") (class "Default")
      (node (ref "D12") (pin "C") (pinfunction "C_C") (pintype "passive"))
      (node (ref "D28") (pin "A") (pinfunction "A_A") (pintype "passive"))
      (node (ref "INB") (pin "P$3") (pinfunction "A_P$3") (pintype "passive"))
      (node (ref "INBCV") (pin "P$1") (pinfunction "2_P$1") (pintype "passive"))
    )
    (net (code "43") (name "Net-(LED2-PadA)") (class "Default")
      (node (ref "LED2") (pin "A") (pinfunction "A_A") (pintype "passive"))
      (node (ref "R1") (pin "1") (pinfunction "1_1") (pintype "passive"))
    )
    (net (code "44") (name "Net-(LED3-PadA)") (class "Default")
      (node (ref "LED3") (pin "A") (pinfunction "A_A") (pintype "passive"))
      (node (ref "R2") (pin "1") (pinfunction "1_1") (pintype "passive"))
    )
    (net (code "45") (name "Net-(MIDIOUT-Pad4)") (class "Default")
      (node (ref "MIDIOUT") (pin "4") (pinfunction "4_4") (pintype "passive"))
      (node (ref "R8") (pin "1") (pinfunction "1_1") (pintype "passive"))
    )
    (net (code "46") (name "Net-(MIDIOUT-Pad5)") (class "Default")
      (node (ref "MIDIOUT") (pin "5") (pinfunction "5_5") (pintype "passive"))
      (node (ref "R3") (pin "2") (pinfunction "2_2") (pintype "passive"))
    )
    (net (code "47") (name "Net-(MIX-A)") (class "Default")
      (node (ref "D13") (pin "C") (pinfunction "C_C") (pintype "passive"))
      (node (ref "D29") (pin "A") (pinfunction "A_A") (pintype "passive"))
      (node (ref "MIX") (pin "P$3") (pinfunction "A_P$3") (pintype "passive"))
      (node (ref "MIXTRANSCV") (pin "P$1") (pinfunction "2_P$1") (pintype "passive"))
    )
    (net (code "48") (name "Net-(OUTCV-2)") (class "Default")
      (node (ref "D14") (pin "C") (pinfunction "C_C") (pintype "passive"))
      (node (ref "D30") (pin "A") (pinfunction "A_A") (pintype "passive"))
      (node (ref "OUTCV") (pin "P$1") (pinfunction "2_P$1") (pintype "passive"))
      (node (ref "OUT_FADE") (pin "P$3") (pinfunction "A_P$3") (pintype "passive"))
    )
    (net (code "49") (name "Net-(TBAR-A)") (class "Default")
      (node (ref "D10") (pin "C") (pinfunction "C_C") (pintype "passive"))
      (node (ref "D26") (pin "A") (pinfunction "A_A") (pintype "passive"))
      (node (ref "TBAR") (pin "P$3") (pinfunction "A_P$3") (pintype "passive"))
      (node (ref "TBARCV") (pin "P$1") (pinfunction "2_P$1") (pintype "passive"))
    )
    (net (code "50") (name "unconnected-(B3-1-PadP$3)") (class "Default")
      (node (ref "B3") (pin "P$3") (pinfunction "1_P$3") (pintype "passive"))
    )
    (net (code "51") (name "unconnected-(B5-Pad3.3V)") (class "Default")
      (node (ref "B5") (pin "3.3V") (pinfunction "3.3V_3.3V") (pintype "bidirectional"))
    )
    (net (code "52") (name "unconnected-(B5-PadAREF)") (class "Default")
      (node (ref "B5") (pin "AREF") (pinfunction "AREF_AREF") (pintype "bidirectional"))
    )
    (net (code "53") (name "unconnected-(B5-PadD0)") (class "Default")
      (node (ref "B5") (pin "D0") (pinfunction "D0_D0") (pintype "bidirectional"))
    )
    (net (code "54") (name "unconnected-(B5-PadD1)") (class "Default")
      (node (ref "B5") (pin "D1") (pinfunction "D1_D1") (pintype "bidirectional"))
    )
    (net (code "55") (name "unconnected-(B5-PadD2)") (class "Default")
      (node (ref "B5") (pin "D2") (pinfunction "D2_D2") (pintype "bidirectional"))
    )
    (net (code "56") (name "unconnected-(B5-PadIOREF)") (class "Default")
      (node (ref "B5") (pin "IOREF") (pinfunction "IOREF_IOREF") (pintype "bidirectional"))
    )
    (net (code "57") (name "unconnected-(B5-PadMISO)") (class "Default")
      (node (ref "B5") (pin "MISO") (pinfunction "MISO_MISO") (pintype "bidirectional"))
    )
    (net (code "58") (name "unconnected-(B5-PadMOSI)") (class "Default")
      (node (ref "B5") (pin "MOSI") (pinfunction "MOSI_MOSI") (pintype "bidirectional"))
    )
    (net (code "59") (name "unconnected-(B5-PadSCK)") (class "Default")
      (node (ref "B5") (pin "SCK") (pinfunction "SCK_SCK") (pintype "bidirectional"))
    )
    (net (code "60") (name "unconnected-(B5-PadSCL)") (class "Default")
      (node (ref "B5") (pin "SCL") (pinfunction "SCL_SCL") (pintype "bidirectional"))
    )
    (net (code "61") (name "unconnected-(B5-PadSDA)") (class "Default")
      (node (ref "B5") (pin "SDA") (pinfunction "SDA_SDA") (pintype "bidirectional"))
    )
    (net (code "62") (name "unconnected-(B5-PadVCC)") (class "Default")
      (node (ref "B5") (pin "VCC") (pinfunction "VCC_VCC") (pintype "bidirectional"))
    )
    (net (code "63") (name "unconnected-(B5-~{RESET}-PadRESET@1)") (class "Default")
      (node (ref "B5") (pin "RESET@1") (pinfunction "~{RESET}_RESET@1") (pintype "bidirectional"))
    )
    (net (code "64") (name "unconnected-(B5-~{RESET}-PadRESET@2)") (class "Default")
      (node (ref "B5") (pin "RESET@2") (pinfunction "~{RESET}_RESET@2") (pintype "bidirectional"))
    )
    (net (code "65") (name "unconnected-(MIDIOUT-Pad1)") (class "Default")
      (node (ref "MIDIOUT") (pin "1") (pinfunction "1_1") (pintype "passive"))
    )
    (net (code "66") (name "unconnected-(MIDIOUT-Pad3)") (class "Default")
      (node (ref "MIDIOUT") (pin "3") (pinfunction "3_3") (pintype "passive"))
    )
    (net (code "67") (name "unconnected-(SV1-Pad1)") (class "Default")
      (node (ref "SV1") (pin "1") (pinfunction "1_1") (pintype "passive"))
    )
    (net (code "68") (name "unconnected-(SV1-Pad2)") (class "Default")
      (node (ref "SV1") (pin "2") (pinfunction "2_2") (pintype "passive"))
    )
    (net (code "69") (name "unconnected-(TRANPORTA-3-PadP$2)") (class "Default")
      (node (ref "TRANPORTA") (pin "P$2") (pinfunction "3_P$2") (pintype "passive"))
    )
    (net (code "70") (name "unconnected-(TRANSPORTB-3-PadP$2)") (class "Default")
      (node (ref "TRANSPORTB") (pin "P$2") (pinfunction "3_P$2") (pintype "passive"))
    )
  )
)
